# power.net
KiCad netlist of a schematic drawn in Altium Designer
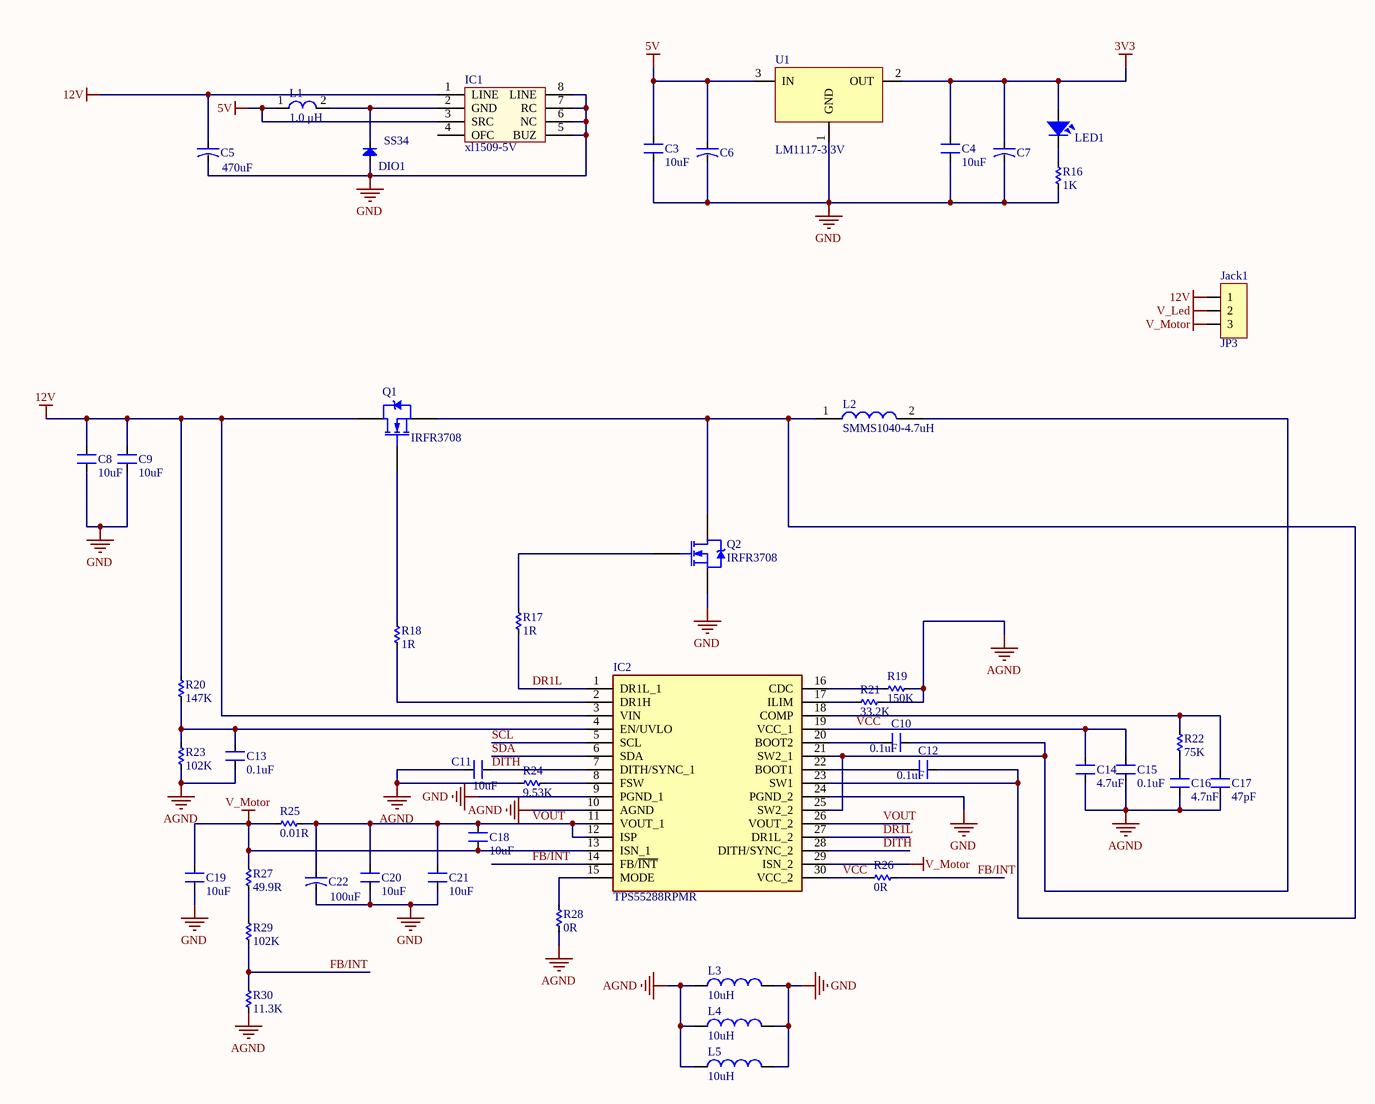
[diagram p0: power.SchDoc]

(export (version "E")
  (design (tool "Eeschema 10.0.6"))
  (components
    (comp (ref "C3")
      (value "10uF")
      (footprint "CN-SMD-0603")
      (description "Tu gom")
      (libsource (lib "LIBTanCN") (part "CN"))
    )
    (comp (ref "C4")
      (value "10uF")
      (footprint "CN-SMD-0603")
      (description "Tu gom")
      (libsource (lib "LIBTanCN") (part "CN"))
    )
    (comp (ref "C5")
      (value "470uF")
      (footprint "CAP-ALU-SMD-6.3x7.7x2.2")
      (description "Polarized Capacitor (Axial)")
      (fields (field (name "PUBLISHER") "Altium Limited"))
      (libsource (lib "LIBTanCN") (part "CN-ALU-SMD"))
    )
    (comp (ref "C6")
      (value "CN-ALU-SMD")
      (footprint "CAP-ALU-SMD-4.5x5x1.4")
      (description "Polarized Capacitor (Axial)")
      (fields (field (name "PUBLISHER") "Altium Limited"))
      (libsource (lib "LIBTanCN") (part "CN-ALU-SMD"))
    )
    (comp (ref "C7")
      (value "CN-ALU-SMD")
      (footprint "CAP-ALU-SMD-4.5x5x1.4")
      (description "Polarized Capacitor (Axial)")
      (fields (field (name "PUBLISHER") "Altium Limited"))
      (libsource (lib "LIBTanCN") (part "CN-ALU-SMD"))
    )
    (comp (ref "C8")
      (value "10uF")
      (footprint "CN-SMD-1206")
      (description "Tu gom")
      (libsource (lib "LIBTanCN") (part "CN"))
    )
    (comp (ref "C9")
      (value "10uF")
      (footprint "CN-SMD-1206")
      (description "Tu gom")
      (libsource (lib "LIBTanCN") (part "CN"))
    )
    (comp (ref "C10")
      (value "0.1uF")
      (footprint "CN-SMD-0603")
      (description "Tu gom")
      (libsource (lib "LIBTanCN") (part "CN"))
    )
    (comp (ref "C11")
      (value "10uF")
      (footprint "CN-SMD-0603")
      (description "Tu gom")
      (libsource (lib "LIBTanCN") (part "CN"))
    )
    (comp (ref "C12")
      (value "0.1uF")
      (footprint "CN-SMD-0603")
      (description "Tu gom")
      (libsource (lib "LIBTanCN") (part "CN"))
    )
    (comp (ref "C13") (value "0.1uF") (footprint "CN-SMD-0603") (libsource (lib "LIBRARY") (part "CN")))
    (comp (ref "C14")
      (value "4.7uF")
      (footprint "CN-SMD-0603")
      (description "Tu gom")
      (libsource (lib "LIBTanCN") (part "CN"))
    )
    (comp (ref "C15")
      (value "0.1uF")
      (footprint "CN-SMD-0603")
      (description "Tu gom")
      (libsource (lib "LIBTanCN") (part "CN"))
    )
    (comp (ref "C16")
      (value "4.7nF")
      (footprint "CN-SMD-0603")
      (description "Tu gom")
      (libsource (lib "LIBTanCN") (part "CN"))
    )
    (comp (ref "C17")
      (value "47pF")
      (footprint "CN-SMD-0603")
      (description "Tu gom")
      (libsource (lib "LIBTanCN") (part "CN"))
    )
    (comp (ref "C18")
      (value "10uF")
      (footprint "CN-SMD-0603")
      (description "Tu gom")
      (libsource (lib "LIBTanCN") (part "CN"))
    )
    (comp (ref "C19")
      (value "10uF")
      (footprint "CN-SMD-0603")
      (description "Tu gom")
      (libsource (lib "LIBTanCN") (part "CN"))
    )
    (comp (ref "C20")
      (value "10uF")
      (footprint "CN-SMD-0603")
      (description "Tu gom")
      (libsource (lib "LIBTanCN") (part "CN"))
    )
    (comp (ref "C21")
      (value "10uF")
      (footprint "CN-SMD-0603")
      (description "Tu gom")
      (libsource (lib "LIBTanCN") (part "CN"))
    )
    (comp (ref "C22")
      (value "100uF")
      (footprint "CAP-ALU-SMD-6.3x7.7x2.2")
      (description "Polarized Capacitor (Axial)")
      (fields (field (name "PUBLISHER") "Altium Limited"))
      (libsource (lib "LIBTanCN") (part "CN-ALU-SMD"))
    )
    (comp (ref "DIO1")
      (value "SS34")
      (footprint "DIO-SMD-106")
      (description "Default Diode")
      (fields (field (name "PUBLISHER") "Altium Limited"))
      (libsource (lib "LIBRARY") (part "Diode SMD"))
    )
    (comp (ref "IC1")
      (value "xl1509-5V")
      (footprint "SO-8")
      (description "Electronic Two-Tone Ringer")
      (libsource (lib "LIBTanCN") (part "LS1240A"))
    )
    (comp (ref "IC2")
      (value "TPS55288RPMR")
      (footprint "SamacSys:TPS55288RPMR")
      (description "Integrated Circuit")
      (fields (field (name "MOUSER PART NUMBER") "595-TPS55288RPMR"))
      (libsource (lib "SamacSys") (part "TPS55288RPMR"))
    )
    (comp (ref "Jack1")
      (value "JP3")
      (footprint "JP3-D1T")
      (description "WR-PHD 2.54 mm Angled Socket Header")
      (fields
        (field (name "MANUFACTURER") "Würth Elektronik eiSos GmbH")
        (field (name "PARTNO") "613003143121")
        (field (name "CREATED BY") "Karrer Zheng")
      )
      (libsource (lib "LIBRARY") (part "JP3"))
    )
    (comp (ref "L1")
      (value "1.0 μH")
      (footprint "L-SMD-M-7.3x4.5")
      (fields
        (field (name "PARTNO") "78477010")
        (field (name "MANUFACTURER") "Wurth Elektronik")
        (field (name "CREATED BY") "Baojun Chen")
      )
      (libsource (lib "LIBRARY") (part "L-SMD-1"))
    )
    (comp (ref "L2")
      (value "SMMS1040-4.7uH")
      (footprint "SamacSys:INDPM115100X400N")
      (description "Inductor")
      (fields (field (name "MANUFACTURER_PART_NUMBER") "SMMS1040-220M"))
      (libsource (lib "SamacSys") (part "SMMS1040-220M"))
    )
    (comp (ref "L3")
      (value "10uH")
      (footprint "Inductor_0603:INDC1608X95N")
      (description "Ind Chip Shielded Multi-Layer 10uH 30% 1MHz Ferrite 50mA 0603 T/R")
      (fields (field (name "MP") "ASMCI-0603-100N-T"))
      (libsource (lib "Inductor_0603") (part "ASMCI-0603-100N-T"))
    )
    (comp (ref "L4")
      (value "10uH")
      (footprint "Inductor_0603:INDC1608X95N")
      (description "Ind Chip Shielded Multi-Layer 10uH 30% 1MHz Ferrite 50mA 0603 T/R")
      (fields (field (name "MP") "ASMCI-0603-100N-T"))
      (libsource (lib "Inductor_0603") (part "ASMCI-0603-100N-T"))
    )
    (comp (ref "L5")
      (value "10uH")
      (footprint "Inductor_0603:INDC1608X95N")
      (description "Ind Chip Shielded Multi-Layer 10uH 30% 1MHz Ferrite 50mA 0603 T/R")
      (fields (field (name "MP") "ASMCI-0603-100N-T"))
      (libsource (lib "Inductor_0603") (part "ASMCI-0603-100N-T"))
    )
    (comp (ref "LED1") (value "LED") (footprint "LED-0805-Blue") (libsource (lib "LIBRARY") (part "LED SMD")))
    (comp (ref "Q1")
      (value "IRFR3708")
      (footprint "TO-252AA_N")
      (description "HEXFET Power MOSFET")
      (fields (field (name "PUBLISHER") "Altium Limited"))
      (libsource (lib "IR Discrete MOSFET - Power") (part "IRFR3910"))
    )
    (comp (ref "Q2")
      (value "IRFR3708")
      (footprint "TO-252AA_N")
      (description "HEXFET Power MOSFET")
      (fields (field (name "PUBLISHER") "Altium Limited"))
      (libsource (lib "IR Discrete MOSFET - Power") (part "IRFR3910"))
    )
    (comp (ref "R16")
      (value "1K")
      (footprint "RES-SMD-0603")
      (description "Resistor")
      (fields
        (field (name "MANUFACTURER") "Generic Components")
        (field (name "PUBLISHER") "Altium Hobart Technology Centre")
      )
      (libsource (lib "LIBRARY") (part "Res-SMD"))
    )
    (comp (ref "R17")
      (value "1R")
      (footprint "RES-SMD-0603")
      (description "Resistor")
      (fields
        (field (name "MANUFACTURER") "Generic Components")
        (field (name "PUBLISHER") "Altium Hobart Technology Centre")
      )
      (libsource (lib "LIBRARY") (part "Res-SMD"))
    )
    (comp (ref "R18")
      (value "1R")
      (footprint "RES-SMD-0603")
      (description "Resistor")
      (fields
        (field (name "MANUFACTURER") "Generic Components")
        (field (name "PUBLISHER") "Altium Hobart Technology Centre")
      )
      (libsource (lib "LIBRARY") (part "Res-SMD"))
    )
    (comp (ref "R19")
      (value "150K")
      (footprint "RES-SMD-0603")
      (description "Resistor")
      (fields
        (field (name "MANUFACTURER") "Generic Components")
        (field (name "PUBLISHER") "Altium Hobart Technology Centre")
      )
      (libsource (lib "LIBRARY") (part "Res-SMD"))
    )
    (comp (ref "R20")
      (value "147K")
      (footprint "RES-SMD-0603")
      (description "Resistor")
      (fields
        (field (name "MANUFACTURER") "Generic Components")
        (field (name "PUBLISHER") "Altium Hobart Technology Centre")
      )
      (libsource (lib "LIBRARY") (part "Res-SMD"))
    )
    (comp (ref "R21")
      (value "33.2K")
      (footprint "RES-SMD-0603")
      (description "Resistor")
      (fields
        (field (name "MANUFACTURER") "Generic Components")
        (field (name "PUBLISHER") "Altium Hobart Technology Centre")
      )
      (libsource (lib "LIBRARY") (part "Res-SMD"))
    )
    (comp (ref "R22")
      (value "75K")
      (footprint "RES-SMD-0603")
      (description "Resistor")
      (fields
        (field (name "MANUFACTURER") "Generic Components")
        (field (name "PUBLISHER") "Altium Hobart Technology Centre")
      )
      (libsource (lib "LIBRARY") (part "Res-SMD"))
    )
    (comp (ref "R23")
      (value "102K")
      (footprint "RES-SMD-0603")
      (description "Resistor")
      (fields
        (field (name "MANUFACTURER") "Generic Components")
        (field (name "PUBLISHER") "Altium Hobart Technology Centre")
      )
      (libsource (lib "LIBRARY") (part "Res-SMD"))
    )
    (comp (ref "R24")
      (value "9.53K")
      (footprint "RES-SMD-0603")
      (description "Resistor")
      (fields
        (field (name "MANUFACTURER") "Generic Components")
        (field (name "PUBLISHER") "Altium Hobart Technology Centre")
      )
      (libsource (lib "LIBRARY") (part "Res-SMD"))
    )
    (comp (ref "R25")
      (value "0.01R")
      (footprint "RES-SMD-1206")
      (description "Resistor")
      (fields
        (field (name "MANUFACTURER") "Generic Components")
        (field (name "PUBLISHER") "Altium Hobart Technology Centre")
      )
      (libsource (lib "LIBRARY") (part "Res-SMD"))
    )
    (comp (ref "R26")
      (value "0R")
      (footprint "RES-SMD-0603")
      (description "Resistor")
      (fields
        (field (name "MANUFACTURER") "Generic Components")
        (field (name "PUBLISHER") "Altium Hobart Technology Centre")
      )
      (libsource (lib "LIBRARY") (part "Res-SMD"))
    )
    (comp (ref "R27")
      (value "49.9R")
      (footprint "RES-SMD-0603")
      (description "Resistor")
      (fields
        (field (name "MANUFACTURER") "Generic Components")
        (field (name "PUBLISHER") "Altium Hobart Technology Centre")
      )
      (libsource (lib "LIBRARY") (part "Res-SMD"))
    )
    (comp (ref "R28")
      (value "0R")
      (footprint "RES-SMD-0603")
      (description "Resistor")
      (fields
        (field (name "MANUFACTURER") "Generic Components")
        (field (name "PUBLISHER") "Altium Hobart Technology Centre")
      )
      (libsource (lib "LIBRARY") (part "Res-SMD"))
    )
    (comp (ref "R29")
      (value "102K")
      (footprint "RES-SMD-0603")
      (description "Resistor")
      (fields
        (field (name "MANUFACTURER") "Generic Components")
        (field (name "PUBLISHER") "Altium Hobart Technology Centre")
      )
      (libsource (lib "LIBRARY") (part "Res-SMD"))
    )
    (comp (ref "R30")
      (value "11.3K")
      (footprint "RES-SMD-0603")
      (description "Resistor")
      (fields
        (field (name "MANUFACTURER") "Generic Components")
        (field (name "PUBLISHER") "Altium Hobart Technology Centre")
      )
      (libsource (lib "LIBRARY") (part "Res-SMD"))
    )
    (comp (ref "U1")
      (value "LM1117-3.3V")
      (footprint "SOT223")
      (description "800mA Low-Dropout Linear Regulator")
      (fields (field (name "CREATOR") "Nguyen Ba Bien"))
      (libsource (lib "LIBRARY") (part "LM1117"))
    )
  )
  (nets
    (net (code "1") (name "/DITH") (class "Default")
      (node (ref "C11") (pin "1") (pinfunction "1_1") (pintype "passive"))
      (node (ref "IC2") (pin "28") (pinfunction "DITH/SYNC_2_28") (pintype "passive"))
      (node (ref "IC2") (pin "7") (pinfunction "DITH/SYNC_1_7") (pintype "passive"))
    )
    (net (code "2") (name "/DR1L") (class "Default")
      (node (ref "IC2") (pin "1") (pinfunction "DR1L_1_1") (pintype "passive"))
      (node (ref "IC2") (pin "27") (pinfunction "DR1L_2_27") (pintype "passive"))
      (node (ref "R17") (pin "2") (pinfunction "2_2") (pintype "passive"))
    )
    (net (code "3") (name "/FB{slash}INT") (class "Default")
      (node (ref "IC2") (pin "14") (pinfunction "FB/~{INT}_14") (pintype "passive"))
      (node (ref "R26") (pin "2") (pinfunction "2_2") (pintype "passive"))
      (node (ref "R29") (pin "2") (pinfunction "2_2") (pintype "passive"))
      (node (ref "R30") (pin "1") (pinfunction "1_1") (pintype "passive"))
    )
    (net (code "4") (name "/SCL") (class "Default")
      (node (ref "IC2") (pin "5") (pinfunction "SCL_5") (pintype "passive"))
    )
    (net (code "5") (name "/SDA") (class "Default")
      (node (ref "IC2") (pin "6") (pinfunction "SDA_6") (pintype "passive"))
    )
    (net (code "6") (name "/VCC") (class "Default")
      (node (ref "C14") (pin "2") (pinfunction "2_2") (pintype "passive"))
      (node (ref "C15") (pin "2") (pinfunction "2_2") (pintype "passive"))
      (node (ref "IC2") (pin "19") (pinfunction "VCC_1_19") (pintype "passive"))
      (node (ref "IC2") (pin "30") (pinfunction "VCC_2_30") (pintype "passive"))
      (node (ref "R26") (pin "1") (pinfunction "1_1") (pintype "passive"))
    )
    (net (code "7") (name "/VOUT") (class "Default")
      (node (ref "C18") (pin "2") (pinfunction "2_2") (pintype "passive"))
      (node (ref "C20") (pin "2") (pinfunction "2_2") (pintype "passive"))
      (node (ref "C21") (pin "2") (pinfunction "2_2") (pintype "passive"))
      (node (ref "C22") (pin "1") (pinfunction "1_1") (pintype "passive"))
      (node (ref "IC2") (pin "11") (pinfunction "VOUT_1_11") (pintype "passive"))
      (node (ref "IC2") (pin "12") (pinfunction "ISP_12") (pintype "passive"))
      (node (ref "IC2") (pin "26") (pinfunction "VOUT_2_26") (pintype "passive"))
      (node (ref "R25") (pin "1") (pinfunction "1_1") (pintype "passive"))
    )
    (net (code "8") (name "3V3") (class "Default")
      (node (ref "C4") (pin "1") (pinfunction "1_1") (pintype "passive"))
      (node (ref "C7") (pin "1") (pinfunction "1_1") (pintype "passive"))
      (node (ref "LED1") (pin "1") (pinfunction "1_1") (pintype "passive"))
      (node (ref "U1") (pin "2") (pinfunction "OUT_2") (pintype "passive"))
    )
    (net (code "9") (name "5V") (class "Default")
      (node (ref "C3") (pin "1") (pinfunction "1_1") (pintype "passive"))
      (node (ref "C6") (pin "1") (pinfunction "1_1") (pintype "passive"))
      (node (ref "IC1") (pin "3") (pinfunction "SRC_3") (pintype "passive"))
      (node (ref "L1") (pin "1") (pinfunction "1_1") (pintype "passive"))
      (node (ref "U1") (pin "3") (pinfunction "IN_3") (pintype "passive"))
    )
    (net (code "10") (name "12V") (class "Default")
      (node (ref "C5") (pin "1") (pinfunction "1_1") (pintype "passive"))
      (node (ref "C8") (pin "2") (pinfunction "2_2") (pintype "passive"))
      (node (ref "C9") (pin "2") (pinfunction "2_2") (pintype "passive"))
      (node (ref "IC1") (pin "1") (pinfunction "LINE_1") (pintype "passive"))
      (node (ref "IC2") (pin "3") (pinfunction "VIN_3") (pintype "passive"))
      (node (ref "Jack1") (pin "1") (pinfunction "1_1") (pintype "passive"))
      (node (ref "Q1") (pin "4") (pinfunction "D_4") (pintype "passive"))
      (node (ref "R20") (pin "1") (pinfunction "1_1") (pintype "passive"))
    )
    (net (code "11") (name "AGND") (class "Default")
      (node (ref "C11") (pin "2") (pinfunction "2_2") (pintype "passive"))
      (node (ref "C13") (pin "1") (pinfunction "1_1") (pintype "passive"))
      (node (ref "C14") (pin "1") (pinfunction "1_1") (pintype "passive"))
      (node (ref "C15") (pin "1") (pinfunction "1_1") (pintype "passive"))
      (node (ref "C16") (pin "2") (pinfunction "2_2") (pintype "passive"))
      (node (ref "C17") (pin "2") (pinfunction "2_2") (pintype "passive"))
      (node (ref "IC2") (pin "10") (pinfunction "AGND_10") (pintype "passive"))
      (node (ref "L3") (pin "1") (pinfunction "1_1") (pintype "passive"))
      (node (ref "L4") (pin "1") (pinfunction "1_1") (pintype "passive"))
      (node (ref "L5") (pin "1") (pinfunction "1_1") (pintype "passive"))
      (node (ref "R19") (pin "2") (pinfunction "2_2") (pintype "passive"))
      (node (ref "R21") (pin "2") (pinfunction "2_2") (pintype "passive"))
      (node (ref "R23") (pin "2") (pinfunction "2_2") (pintype "passive"))
      (node (ref "R24") (pin "1") (pinfunction "1_1") (pintype "passive"))
      (node (ref "R28") (pin "2") (pinfunction "2_2") (pintype "passive"))
      (node (ref "R30") (pin "2") (pinfunction "2_2") (pintype "passive"))
    )
    (net (code "12") (name "GND") (class "Default")
      (node (ref "C19") (pin "1") (pinfunction "1_1") (pintype "passive"))
      (node (ref "C20") (pin "1") (pinfunction "1_1") (pintype "passive"))
      (node (ref "C21") (pin "1") (pinfunction "1_1") (pintype "passive"))
      (node (ref "C22") (pin "2") (pinfunction "2_2") (pintype "passive"))
      (node (ref "C3") (pin "2") (pinfunction "2_2") (pintype "passive"))
      (node (ref "C4") (pin "2") (pinfunction "2_2") (pintype "passive"))
      (node (ref "C5") (pin "2") (pinfunction "2_2") (pintype "passive"))
      (node (ref "C6") (pin "2") (pinfunction "2_2") (pintype "passive"))
      (node (ref "C7") (pin "2") (pinfunction "2_2") (pintype "passive"))
      (node (ref "C8") (pin "1") (pinfunction "1_1") (pintype "passive"))
      (node (ref "C9") (pin "1") (pinfunction "1_1") (pintype "passive"))
      (node (ref "DIO1") (pin "1") (pinfunction "A_1") (pintype "passive"))
      (node (ref "IC1") (pin "5") (pinfunction "BUZ_5") (pintype "passive"))
      (node (ref "IC1") (pin "6") (pinfunction "NC_6") (pintype "passive"))
      (node (ref "IC1") (pin "7") (pinfunction "RC_7") (pintype "passive"))
      (node (ref "IC1") (pin "8") (pinfunction "LINE_8") (pintype "passive"))
      (node (ref "IC2") (pin "24") (pinfunction "PGND_2_24") (pintype "passive"))
      (node (ref "IC2") (pin "9") (pinfunction "PGND_1_9") (pintype "passive"))
      (node (ref "L3") (pin "2") (pinfunction "2_2") (pintype "passive"))
      (node (ref "L4") (pin "2") (pinfunction "2_2") (pintype "passive"))
      (node (ref "L5") (pin "2") (pinfunction "2_2") (pintype "passive"))
      (node (ref "Q2") (pin "3") (pinfunction "S_3") (pintype "passive"))
      (node (ref "R16") (pin "2") (pinfunction "2_2") (pintype "passive"))
      (node (ref "U1") (pin "1") (pinfunction "GND_1") (pintype "passive"))
    )
    (net (code "13") (name "Net-(C16-Pad1)") (class "Default")
      (node (ref "C16") (pin "1") (pinfunction "1_1") (pintype "passive"))
      (node (ref "R22") (pin "2") (pinfunction "2_2") (pintype "passive"))
    )
    (net (code "14") (name "Net-(DIO1-K)") (class "Default")
      (node (ref "DIO1") (pin "2") (pinfunction "K_2") (pintype "passive"))
      (node (ref "IC1") (pin "2") (pinfunction "GND_2") (pintype "passive"))
      (node (ref "L1") (pin "2") (pinfunction "2_2") (pintype "passive"))
    )
    (net (code "15") (name "Net-(IC2-BOOT1)") (class "Default")
      (node (ref "C12") (pin "2") (pinfunction "2_2") (pintype "passive"))
      (node (ref "IC2") (pin "22") (pinfunction "BOOT1_22") (pintype "passive"))
    )
    (net (code "16") (name "Net-(IC2-BOOT2)") (class "Default")
      (node (ref "C10") (pin "2") (pinfunction "2_2") (pintype "passive"))
      (node (ref "IC2") (pin "20") (pinfunction "BOOT2_20") (pintype "passive"))
    )
    (net (code "17") (name "Net-(IC2-CDC)") (class "Default")
      (node (ref "IC2") (pin "16") (pinfunction "CDC_16") (pintype "passive"))
      (node (ref "R19") (pin "1") (pinfunction "1_1") (pintype "passive"))
    )
    (net (code "18") (name "Net-(IC2-COMP)") (class "Default")
      (node (ref "C17") (pin "1") (pinfunction "1_1") (pintype "passive"))
      (node (ref "IC2") (pin "18") (pinfunction "COMP_18") (pintype "passive"))
      (node (ref "R22") (pin "1") (pinfunction "1_1") (pintype "passive"))
    )
    (net (code "19") (name "Net-(IC2-DR1H)") (class "Default")
      (node (ref "IC2") (pin "2") (pinfunction "DR1H_2") (pintype "passive"))
      (node (ref "R18") (pin "2") (pinfunction "2_2") (pintype "passive"))
    )
    (net (code "20") (name "Net-(IC2-EN{slash}UVLO)") (class "Default")
      (node (ref "C13") (pin "2") (pinfunction "2_2") (pintype "passive"))
      (node (ref "IC2") (pin "4") (pinfunction "EN/UVLO_4") (pintype "passive"))
      (node (ref "R20") (pin "2") (pinfunction "2_2") (pintype "passive"))
      (node (ref "R23") (pin "1") (pinfunction "1_1") (pintype "passive"))
    )
    (net (code "21") (name "Net-(IC2-FSW)") (class "Default")
      (node (ref "IC2") (pin "8") (pinfunction "FSW_8") (pintype "passive"))
      (node (ref "R24") (pin "2") (pinfunction "2_2") (pintype "passive"))
    )
    (net (code "22") (name "Net-(IC2-ILIM)") (class "Default")
      (node (ref "IC2") (pin "17") (pinfunction "ILIM_17") (pintype "passive"))
      (node (ref "R21") (pin "1") (pinfunction "1_1") (pintype "passive"))
    )
    (net (code "23") (name "Net-(IC2-MODE)") (class "Default")
      (node (ref "IC2") (pin "15") (pinfunction "MODE_15") (pintype "passive"))
      (node (ref "R28") (pin "1") (pinfunction "1_1") (pintype "passive"))
    )
    (net (code "24") (name "Net-(IC2-SW1)") (class "Default")
      (node (ref "C12") (pin "1") (pinfunction "1_1") (pintype "passive"))
      (node (ref "IC2") (pin "23") (pinfunction "SW1_23") (pintype "passive"))
      (node (ref "L2") (pin "1") (pinfunction "1_1") (pintype "passive"))
      (node (ref "Q1") (pin "3") (pinfunction "S_3") (pintype "passive"))
      (node (ref "Q2") (pin "4") (pinfunction "D_4") (pintype "passive"))
    )
    (net (code "25") (name "Net-(IC2-SW2_1)") (class "Default")
      (node (ref "C10") (pin "1") (pinfunction "1_1") (pintype "passive"))
      (node (ref "IC2") (pin "21") (pinfunction "SW2_1_21") (pintype "passive"))
      (node (ref "IC2") (pin "25") (pinfunction "SW2_2_25") (pintype "passive"))
      (node (ref "L2") (pin "2") (pinfunction "2_2") (pintype "passive"))
    )
    (net (code "26") (name "Net-(LED1-Pad2)") (class "Default")
      (node (ref "LED1") (pin "2") (pinfunction "2_2") (pintype "passive"))
      (node (ref "R16") (pin "1") (pinfunction "1_1") (pintype "passive"))
    )
    (net (code "27") (name "Net-(Q1-G)") (class "Default")
      (node (ref "Q1") (pin "1") (pinfunction "G_1") (pintype "passive"))
      (node (ref "R18") (pin "1") (pinfunction "1_1") (pintype "passive"))
    )
    (net (code "28") (name "Net-(Q2-G)") (class "Default")
      (node (ref "Q2") (pin "1") (pinfunction "G_1") (pintype "passive"))
      (node (ref "R17") (pin "1") (pinfunction "1_1") (pintype "passive"))
    )
    (net (code "29") (name "Net-(R27-Pad2)") (class "Default")
      (node (ref "R27") (pin "2") (pinfunction "2_2") (pintype "passive"))
      (node (ref "R29") (pin "1") (pinfunction "1_1") (pintype "passive"))
    )
    (net (code "30") (name "V_Led") (class "Default")
      (node (ref "Jack1") (pin "2") (pinfunction "2_2") (pintype "passive"))
    )
    (net (code "31") (name "V_Motor") (class "Default")
      (node (ref "C18") (pin "1") (pinfunction "1_1") (pintype "passive"))
      (node (ref "C19") (pin "2") (pinfunction "2_2") (pintype "passive"))
      (node (ref "IC2") (pin "13") (pinfunction "ISN_1_13") (pintype "passive"))
      (node (ref "IC2") (pin "29") (pinfunction "ISN_2_29") (pintype "passive"))
      (node (ref "Jack1") (pin "3") (pinfunction "3_3") (pintype "passive"))
      (node (ref "R25") (pin "2") (pinfunction "2_2") (pintype "passive"))
      (node (ref "R27") (pin "1") (pinfunction "1_1") (pintype "passive"))
    )
    (net (code "32") (name "unconnected-(IC1-OFC-Pad4)") (class "Default")
      (node (ref "IC1") (pin "4") (pinfunction "OFC_4") (pintype "passive"))
    )
  )
)
